# LDO.net
KiCad netlist of a schematic drawn in Altium Designer
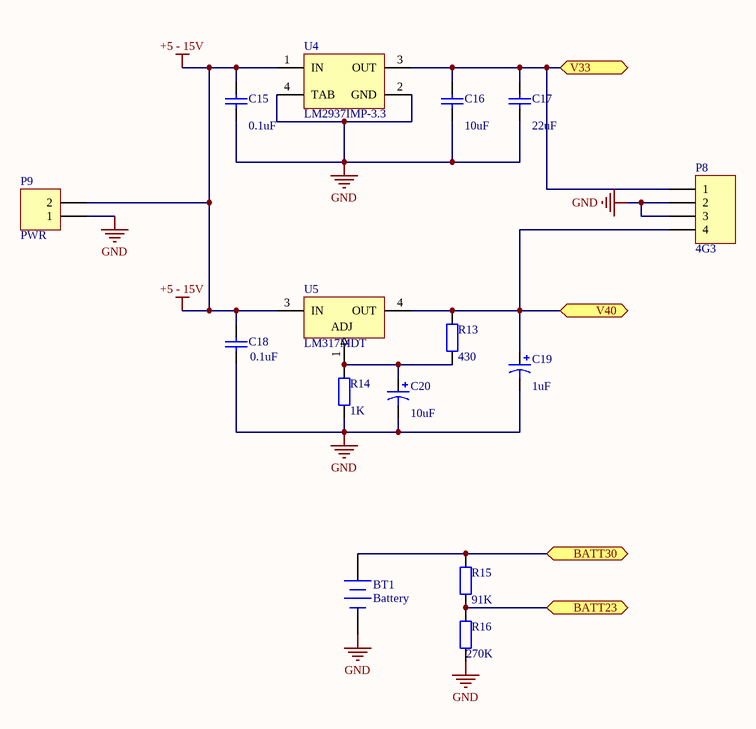
[diagram p0: LDO.SchDoc]

(export (version "E")
  (design (tool "Eeschema 10.0.6"))
  (components
    (comp (ref "BT1")
      (value "Battery")
      (footprint "Edge Connector")
      (description "Multicell Battery")
      (fields (field (name "PUBLISHER") "Altium Limited"))
      (libsource (lib "Miscellaneous Devices") (part "Battery"))
    )
    (comp (ref "C15")
      (value "0.1uF")
      (footprint "RAD-0.1")
      (description "Capacitor")
      (fields (field (name "Comment") "Cap") (field (name "PUBLISHER") "Altium Limited"))
      (libsource (lib "Miscellaneous Devices") (part "Cap"))
    )
    (comp (ref "C16")
      (value "10uF")
      (footprint "R38")
      (description "Capacitor")
      (fields (field (name "Comment") "Cap") (field (name "PUBLISHER") "Altium Limited"))
      (libsource (lib "Miscellaneous Devices") (part "Cap"))
    )
    (comp (ref "C17")
      (value "22uF")
      (footprint "R38")
      (description "Capacitor")
      (fields (field (name "Comment") "Cap") (field (name "PUBLISHER") "Altium Limited"))
      (libsource (lib "Miscellaneous Devices") (part "Cap"))
    )
    (comp (ref "C18")
      (value "0.1uF")
      (footprint "RAD-0.1")
      (description "Capacitor")
      (fields (field (name "Comment") "Cap") (field (name "PUBLISHER") "Altium Limited"))
      (libsource (lib "Miscellaneous Devices") (part "Cap"))
    )
    (comp (ref "C19")
      (value "1uF")
      (footprint "R38")
      (description "Polarized Capacitor (Radial)")
      (fields (field (name "Comment") "Cap Pol1") (field (name "PUBLISHER") "Altium Limited"))
      (libsource (lib "Miscellaneous Devices") (part "Cap Pol1"))
    )
    (comp (ref "C20")
      (value "10uF")
      (footprint "R38")
      (description "Polarized Capacitor (Radial)")
      (fields (field (name "Comment") "Cap Pol1") (field (name "PUBLISHER") "Altium Limited"))
      (libsource (lib "Miscellaneous Devices") (part "Cap Pol1"))
    )
    (comp (ref "P8")
      (value "4G3")
      (footprint "HDR1X4")
      (description "Header, 4-Pin, Right Angle")
      (fields (field (name "PUBLISHER") "Altium Limited"))
      (libsource (lib "Miscellaneous Connectors") (part "Header 4H"))
    )
    (comp (ref "P9")
      (value "PWR")
      (footprint "HDR1X2H")
      (description "Header, 2-Pin, Right Angle")
      (fields (field (name "PUBLISHER") "Altium Limited"))
      (libsource (lib "Miscellaneous Connectors") (part "Header 2H"))
    )
    (comp (ref "R13")
      (value "430")
      (footprint "AXIAL-0.4")
      (description "Resistor")
      (fields (field (name "Comment") "Res2") (field (name "PUBLISHER") "Altium Limited"))
      (libsource (lib "Miscellaneous Devices") (part "Res2"))
    )
    (comp (ref "R14")
      (value "1K")
      (footprint "AXIAL-0.4")
      (description "Resistor")
      (fields (field (name "Comment") "Res2") (field (name "PUBLISHER") "Altium Limited"))
      (libsource (lib "Miscellaneous Devices") (part "Res2"))
    )
    (comp (ref "R15")
      (value "91K")
      (footprint "AXIAL-0.4")
      (description "Resistor")
      (fields (field (name "Comment") "Res2") (field (name "PUBLISHER") "Altium Limited"))
      (libsource (lib "Miscellaneous Devices") (part "Res2"))
    )
    (comp (ref "R16")
      (value "270K")
      (footprint "AXIAL-0.4")
      (description "Resistor")
      (fields (field (name "Comment") "Res2") (field (name "PUBLISHER") "Altium Limited"))
      (libsource (lib "Miscellaneous Devices") (part "Res2"))
    )
    (comp (ref "U4")
      (value "LM2937IMP-3.3")
      (footprint "MP04A_N")
      (description "500 mA Low Dropout Regulator")
      (fields
        (field (name "MANUFACTURER") "National Semiconductor")
        (field (name "DIGIKEYPARTNUMBER") "LM2937IMP-3.3CT-ND")
        (field (name "PUBLISHER") "Altium Limited")
      )
      (libsource (lib "NSC LDO") (part "LM2937IMP-3.3"))
    )
    (comp (ref "U5")
      (value "LM317MDT")
      (footprint "TD03B_N")
      (description "3-Terminal Adjustable Regulator")
      (fields
        (field (name "MANUFACTURER") "National Semiconductor")
        (field (name "DIGIKEYPARTNUMBER") "LM317MDTNS-ND")
        (field (name "PUBLISHER") "Altium Limited")
      )
      (libsource (lib "NSC LDO") (part "LM317MDT"))
    )
  )
  (nets
    (net (code "1") (name "+5 - 15V") (class "Default")
      (node (ref "C15") (pin "2") (pinfunction "2_2") (pintype "passive"))
      (node (ref "C18") (pin "2") (pinfunction "2_2") (pintype "passive"))
      (node (ref "P9") (pin "2") (pinfunction "2_2") (pintype "passive"))
      (node (ref "U4") (pin "1") (pinfunction "IN_1") (pintype "power_in"))
      (node (ref "U5") (pin "3") (pinfunction "IN_3") (pintype "power_in"))
    )
    (net (code "2") (name "/BATT23") (class "Default")
      (node (ref "R15") (pin "1") (pinfunction "1_1") (pintype "passive"))
      (node (ref "R16") (pin "2") (pinfunction "2_2") (pintype "passive"))
    )
    (net (code "3") (name "/BATT30") (class "Default")
      (node (ref "BT1") (pin "1") (pinfunction "+_1") (pintype "passive"))
      (node (ref "R15") (pin "2") (pinfunction "2_2") (pintype "passive"))
    )
    (net (code "4") (name "/V33") (class "Default")
      (node (ref "C16") (pin "2") (pinfunction "2_2") (pintype "passive"))
      (node (ref "C17") (pin "2") (pinfunction "2_2") (pintype "passive"))
      (node (ref "P8") (pin "1") (pinfunction "1_1") (pintype "passive"))
      (node (ref "U4") (pin "3") (pinfunction "OUT_3") (pintype "power_in"))
    )
    (net (code "5") (name "/V40") (class "Default")
      (node (ref "C19") (pin "1") (pinfunction "1_1") (pintype "passive"))
      (node (ref "P8") (pin "4") (pinfunction "4_4") (pintype "passive"))
      (node (ref "R13") (pin "2") (pinfunction "2_2") (pintype "passive"))
      (node (ref "U5") (pin "4") (pinfunction "OUT_4") (pintype "power_in"))
    )
    (net (code "6") (name "GND") (class "Default")
      (node (ref "BT1") (pin "2") (pinfunction "-_2") (pintype "passive"))
      (node (ref "C15") (pin "1") (pinfunction "1_1") (pintype "passive"))
      (node (ref "C16") (pin "1") (pinfunction "1_1") (pintype "passive"))
      (node (ref "C17") (pin "1") (pinfunction "1_1") (pintype "passive"))
      (node (ref "C18") (pin "1") (pinfunction "1_1") (pintype "passive"))
      (node (ref "C19") (pin "2") (pinfunction "2_2") (pintype "passive"))
      (node (ref "C20") (pin "2") (pinfunction "2_2") (pintype "passive"))
      (node (ref "P8") (pin "2") (pinfunction "2_2") (pintype "passive"))
      (node (ref "P8") (pin "3") (pinfunction "3_3") (pintype "passive"))
      (node (ref "P9") (pin "1") (pinfunction "1_1") (pintype "passive"))
      (node (ref "R14") (pin "1") (pinfunction "1_1") (pintype "passive"))
      (node (ref "R16") (pin "1") (pinfunction "1_1") (pintype "passive"))
      (node (ref "U4") (pin "2") (pinfunction "GND_2") (pintype "power_in"))
      (node (ref "U4") (pin "4") (pinfunction "TAB_4") (pintype "power_in"))
    )
    (net (code "7") (name "Net-(U5-ADJ)") (class "Default")
      (node (ref "C20") (pin "1") (pinfunction "1_1") (pintype "passive"))
      (node (ref "R13") (pin "1") (pinfunction "1_1") (pintype "passive"))
      (node (ref "R14") (pin "2") (pinfunction "2_2") (pintype "passive"))
      (node (ref "U5") (pin "1") (pinfunction "ADJ_1") (pintype "input"))
    )
  )
)
